# DataMergeBoardTop.net
KiCad netlist of a schematic drawn in Altium Designer
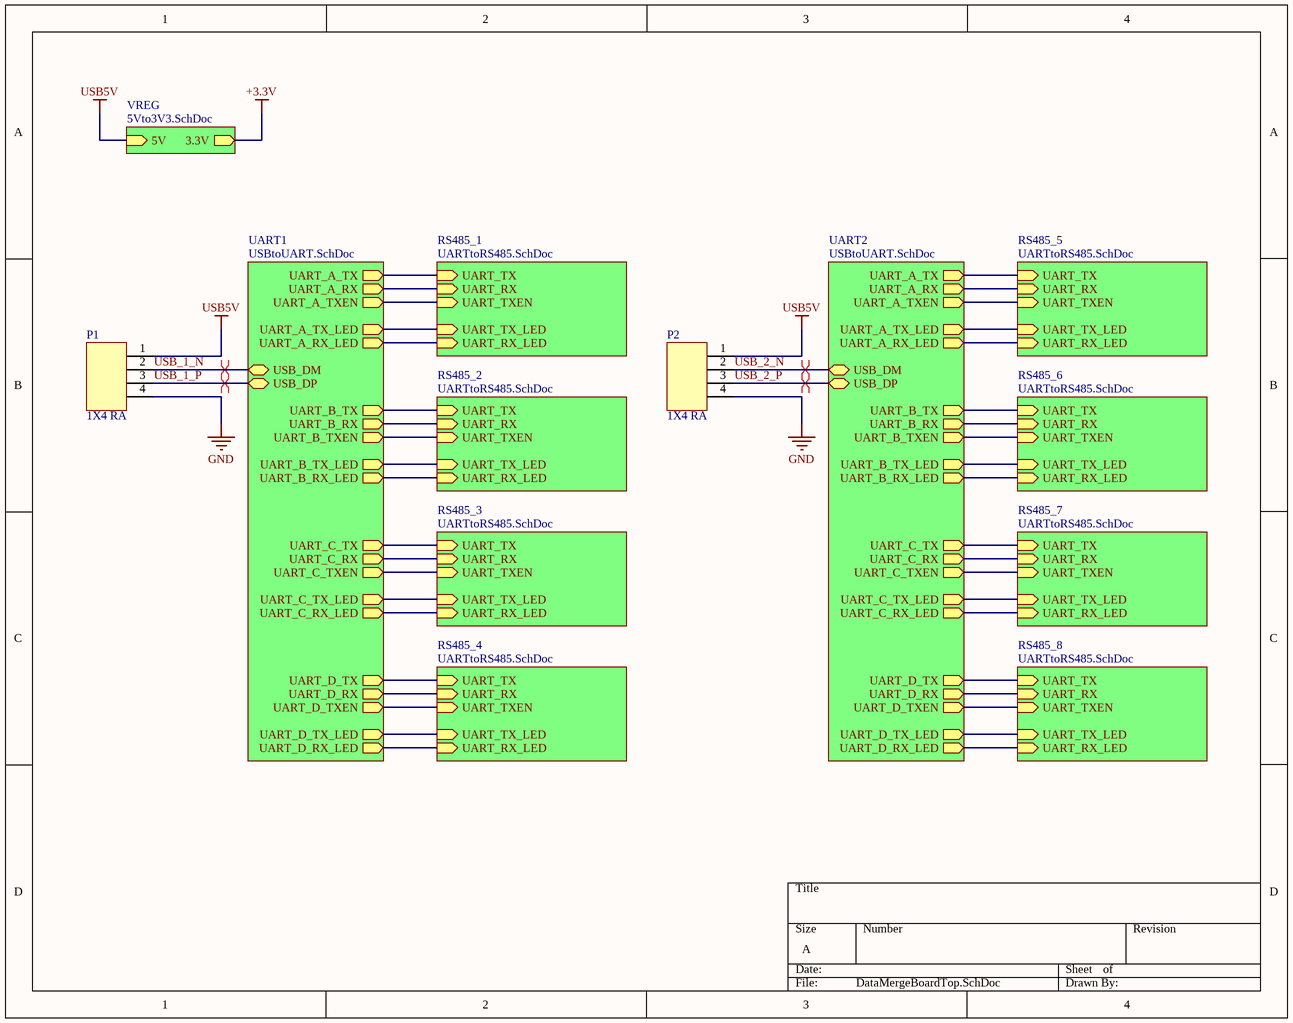
[diagram p0: DataMergeBoardTop.SchDoc]

(export (version "E")
  (design (tool "Eeschema 10.0.6"))
  (components
    (comp (ref "P1")
      (value "1X4 RA")
      (footprint "MOLEX-HDR-1X4-SHERLOCK-RA")
      (description "CONN HEADER 4POS 2MM R/A TIN")
      (libsource (lib "Connectors") (part "MOLEX-HDR-1x4-SHERLOCK_RA"))
    )
    (comp (ref "P2")
      (value "1X4 RA")
      (footprint "MOLEX-HDR-1X4-SHERLOCK-RA")
      (description "CONN HEADER 4POS 2MM R/A TIN")
      (libsource (lib "Connectors") (part "MOLEX-HDR-1x4-SHERLOCK_RA"))
    )
  )
  (nets
    (net (code "42") (name "/USB_1_N") (class "Default")
      (node (ref "P1") (pin "2") (pinfunction "2_2") (pintype "passive"))
    )
    (net (code "43") (name "/USB_1_P") (class "Default")
      (node (ref "P1") (pin "3") (pinfunction "3_3") (pintype "passive"))
    )
    (net (code "44") (name "/USB_2_N") (class "Default")
      (node (ref "P2") (pin "2") (pinfunction "2_2") (pintype "passive"))
    )
    (net (code "45") (name "/USB_2_P") (class "Default")
      (node (ref "P2") (pin "3") (pinfunction "3_3") (pintype "passive"))
    )
    (net (code "46") (name "GND") (class "Default")
      (node (ref "P1") (pin "4") (pinfunction "4_4") (pintype "passive"))
      (node (ref "P2") (pin "4") (pinfunction "4_4") (pintype "passive"))
    )
    (net (code "47") (name "USB5V") (class "Default")
      (node (ref "P1") (pin "1") (pinfunction "1_1") (pintype "passive"))
      (node (ref "P2") (pin "1") (pinfunction "1_1") (pintype "passive"))
    )
  )
)
